# SCH_-_Compute_Flash.net
KiCad netlist of a schematic drawn in Altium Designer
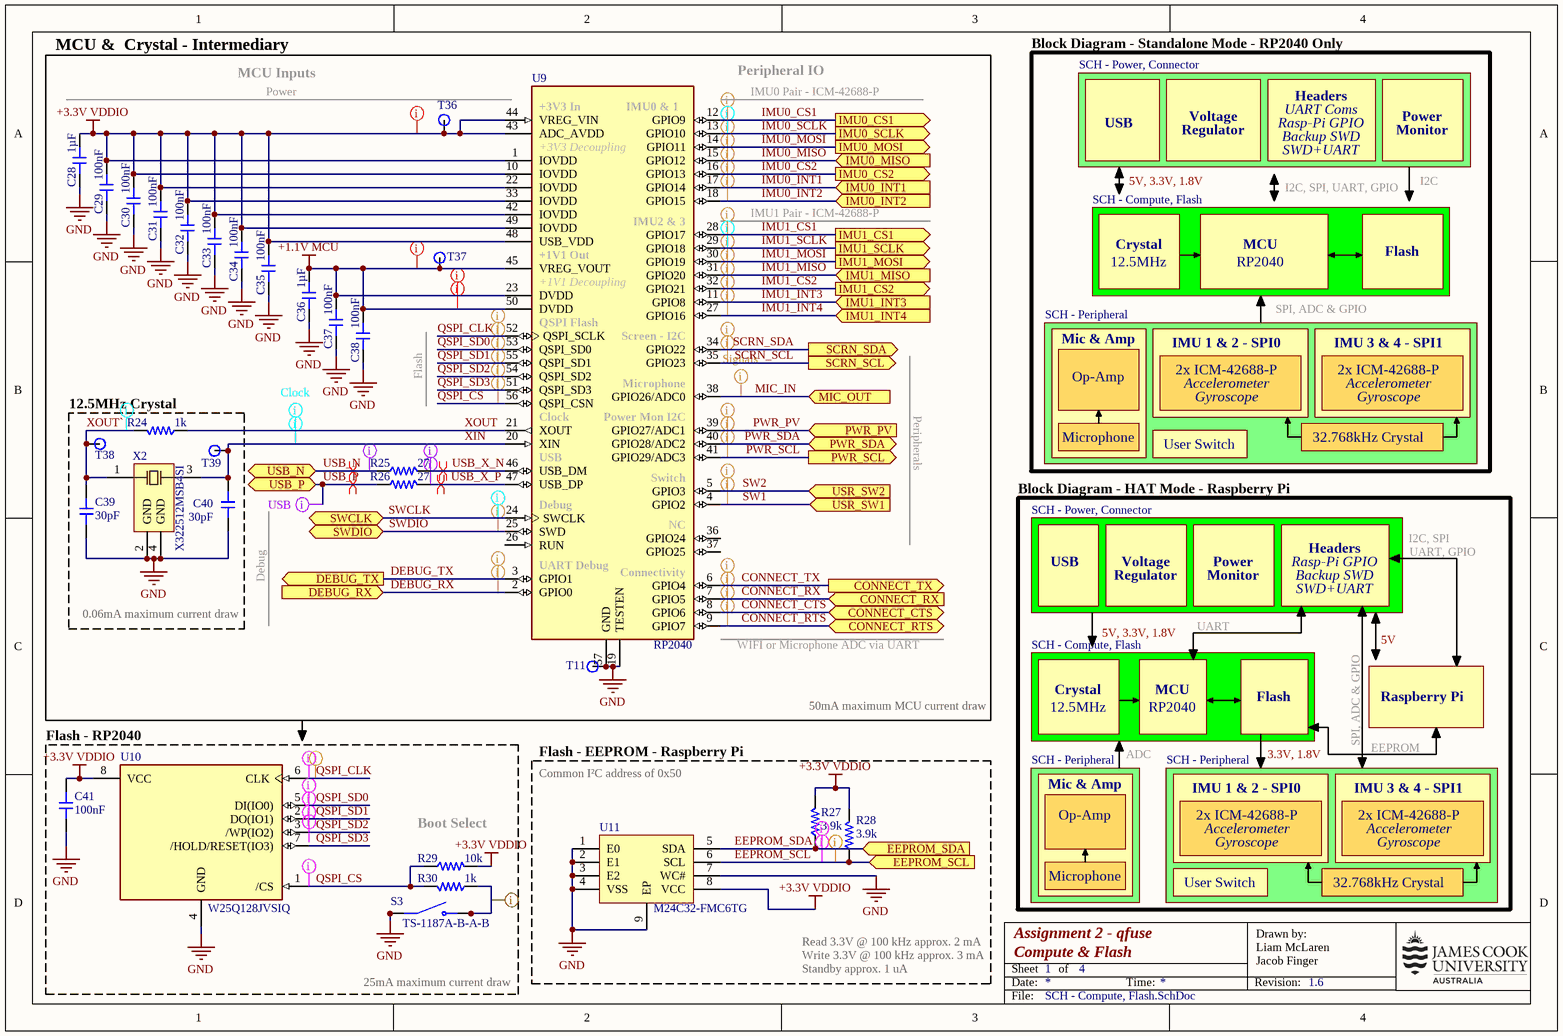
[diagram p0: SCH - Compute, Flash.SchDoc]

(export (version "E")
  (design (tool "Eeschema 10.0.6"))
  (components
    (comp (ref "C28")
      (value "1µF")
      (footprint "CAP-0402")
      (description "Capacitor, Ceramic (MLCC), 1uF, ±10%, 25V, X5R, ±10%, SMD 0402")
      (fields
        (field (name "JLCPCB BASIC PART") "Yes")
        (field (name "MANUFACTURER") "Samsung Electro-Mechanics")
      )
      (libsource (lib "Finmac Systems") (part "GRM21BR61H106KE43L"))
    )
    (comp (ref "C29")
      (value "100nF")
      (footprint "CAP-0402")
      (description "Capacitor, Ceramic (MLCC), 100nF, ±10%, 50V, X7R, ±10%, SMD 0402")
      (fields
        (field (name "MANUFACTURER PART NUMBER") "CL05B104KB54PNC")
        (field (name "MANUFACTURER") "Samsung Electro-Mechanics")
      )
      (libsource (lib "Finmac Systems") (part "GRM21BR61H106KE43L"))
    )
    (comp (ref "C30")
      (value "100nF")
      (footprint "CAP-0402")
      (description "Capacitor, Ceramic (MLCC), 100nF, ±10%, 50V, X7R, ±10%, SMD 0402")
      (fields
        (field (name "MANUFACTURER PART NUMBER") "CL05B104KB54PNC")
        (field (name "MANUFACTURER") "Samsung Electro-Mechanics")
      )
      (libsource (lib "Finmac Systems") (part "GRM21BR61H106KE43L"))
    )
    (comp (ref "C31")
      (value "100nF")
      (footprint "CAP-0402")
      (description "Capacitor, Ceramic (MLCC), 100nF, ±10%, 50V, X7R, ±10%, SMD 0402")
      (fields
        (field (name "MANUFACTURER PART NUMBER") "CL05B104KB54PNC")
        (field (name "MANUFACTURER") "Samsung Electro-Mechanics")
      )
      (libsource (lib "Finmac Systems") (part "GRM21BR61H106KE43L"))
    )
    (comp (ref "C32")
      (value "100nF")
      (footprint "CAP-0402")
      (description "Capacitor, Ceramic (MLCC), 100nF, ±10%, 50V, X7R, ±10%, SMD 0402")
      (fields
        (field (name "MANUFACTURER PART NUMBER") "CL05B104KB54PNC")
        (field (name "MANUFACTURER") "Samsung Electro-Mechanics")
      )
      (libsource (lib "Finmac Systems") (part "GRM21BR61H106KE43L"))
    )
    (comp (ref "C33")
      (value "100nF")
      (footprint "CAP-0402")
      (description "Capacitor, Ceramic (MLCC), 100nF, ±10%, 50V, X7R, ±10%, SMD 0402")
      (fields
        (field (name "MANUFACTURER PART NUMBER") "CL05B104KB54PNC")
        (field (name "MANUFACTURER") "Samsung Electro-Mechanics")
      )
      (libsource (lib "Finmac Systems") (part "GRM21BR61H106KE43L"))
    )
    (comp (ref "C34")
      (value "100nF")
      (footprint "CAP-0402")
      (description "Capacitor, Ceramic (MLCC), 100nF, ±10%, 50V, X7R, ±10%, SMD 0402")
      (fields
        (field (name "MANUFACTURER PART NUMBER") "CL05B104KB54PNC")
        (field (name "MANUFACTURER") "Samsung Electro-Mechanics")
      )
      (libsource (lib "Finmac Systems") (part "GRM21BR61H106KE43L"))
    )
    (comp (ref "C35")
      (value "100nF")
      (footprint "CAP-0402")
      (description "Capacitor, Ceramic (MLCC), 100nF, ±10%, 50V, X7R, ±10%, SMD 0402")
      (fields
        (field (name "MANUFACTURER PART NUMBER") "CL05B104KB54PNC")
        (field (name "MANUFACTURER") "Samsung Electro-Mechanics")
      )
      (libsource (lib "Finmac Systems") (part "GRM21BR61H106KE43L"))
    )
    (comp (ref "C36")
      (value "1µF")
      (footprint "CAP-0402")
      (description "Capacitor, Ceramic (MLCC), 1uF, ±10%, 25V, X5R, ±10%, SMD 0402")
      (fields
        (field (name "JLCPCB BASIC PART") "Yes")
        (field (name "MANUFACTURER") "Samsung Electro-Mechanics")
      )
      (libsource (lib "Finmac Systems") (part "GRM21BR61H106KE43L"))
    )
    (comp (ref "C37")
      (value "100nF")
      (footprint "CAP-0402")
      (description "Capacitor, Ceramic (MLCC), 100nF, ±10%, 50V, X7R, ±10%, SMD 0402")
      (fields
        (field (name "MANUFACTURER PART NUMBER") "CL05B104KB54PNC")
        (field (name "MANUFACTURER") "Samsung Electro-Mechanics")
      )
      (libsource (lib "Finmac Systems") (part "GRM21BR61H106KE43L"))
    )
    (comp (ref "C38")
      (value "100nF")
      (footprint "CAP-0402")
      (description "Capacitor, Ceramic (MLCC), 100nF, ±10%, 50V, X7R, ±10%, SMD 0402")
      (fields
        (field (name "MANUFACTURER PART NUMBER") "CL05B104KB54PNC")
        (field (name "MANUFACTURER") "Samsung Electro-Mechanics")
      )
      (libsource (lib "Finmac Systems") (part "GRM21BR61H106KE43L"))
    )
    (comp (ref "C39")
      (value "30pF")
      (footprint "CAP-0603")
      (description "Capacitor, Ceramic (MLCC), 30pF, ±5%, 50V, C0G, ±5%, SMD 0603")
      (fields (field (name "JLCPCB PART NUMBER") "C1658") (field (name "TOLERANCE") "5%"))
      (libsource (lib "Finmac Systems") (part "GRM21BR61H106KE43L"))
    )
    (comp (ref "C40")
      (value "30pF")
      (footprint "CAP-0603")
      (description "Capacitor, Ceramic (MLCC), 30pF, ±5%, 50V, C0G, ±5%, SMD 0603")
      (fields (field (name "JLCPCB PART NUMBER") "C1658") (field (name "TOLERANCE") "5%"))
      (libsource (lib "Finmac Systems") (part "GRM21BR61H106KE43L"))
    )
    (comp (ref "C41")
      (value "100nF")
      (footprint "CAP-0402")
      (description "Capacitor, Ceramic (MLCC), 100nF, ±10%, 50V, X7R, ±10%, SMD 0402")
      (fields
        (field (name "MANUFACTURER PART NUMBER") "CL05B104KB54PNC")
        (field (name "MANUFACTURER") "Samsung Electro-Mechanics")
      )
      (libsource (lib "Finmac Systems") (part "GRM21BR61H106KE43L"))
    )
    (comp (ref "R24")
      (value "1k")
      (footprint "RES-0402")
      (description "Resistor, 1kΩ, ±1%, 62.5mW, 50V, ±100ppm/℃, -55℃~+155℃, SMD 0402")
      (fields (field (name "JLCPCB PART NUMBER") "C11702") (field (name "JLCPCB BASIC PART") "Yes"))
      (libsource (lib "Finmac Systems") (part "1206W4F7500T5E"))
    )
    (comp (ref "R25")
      (value "27")
      (footprint "RES-0603")
      (description "Resistor, 27Ω, ±1%, 100mW, 75V, ±200ppm/℃, -55℃~+155℃, SMD 0603")
      (fields (field (name "MANUFACTURER") "Uniroyal") (field (name "JLCPCB PART NUMBER") "C25190"))
      (libsource (lib "Finmac Systems") (part "1206W4F7500T5E"))
    )
    (comp (ref "R26")
      (value "27")
      (footprint "RES-0603")
      (description "Resistor, 27Ω, ±1%, 100mW, 75V, ±200ppm/℃, -55℃~+155℃, SMD 0603")
      (fields (field (name "MANUFACTURER") "Uniroyal") (field (name "JLCPCB PART NUMBER") "C25190"))
      (libsource (lib "Finmac Systems") (part "1206W4F7500T5E"))
    )
    (comp (ref "R27")
      (value "3.9k")
      (footprint "RES-0402")
      (description "Resistor, 3.9kΩ, ±1%, 62.5mW, 50V, ±100ppm/℃, -55℃~+155℃, SMD 0402")
      (fields (field (name "MANUFACTURER PART NUMBER") "0402WGF3901TCE") (field (name "TOLERANCE") "1%"))
      (libsource (lib "Finmac Systems") (part "1206W4F7500T5E"))
    )
    (comp (ref "R28")
      (value "3.9k")
      (footprint "RES-0402")
      (description "Resistor, 3.9kΩ, ±1%, 62.5mW, 50V, ±100ppm/℃, -55℃~+155℃, SMD 0402")
      (fields (field (name "MANUFACTURER PART NUMBER") "0402WGF3901TCE") (field (name "TOLERANCE") "1%"))
      (libsource (lib "Finmac Systems") (part "1206W4F7500T5E"))
    )
    (comp (ref "R29")
      (value "10k")
      (footprint "RES-0402")
      (description "Resistor, 10kΩ, ±1%, 62.5mW, 50V, ±100ppm/℃, -55℃~+155℃, SMD 0402")
      (fields (field (name "JLCPCB BASIC PART") "Yes") (field (name "MANUFACTURER") "Uniroyal"))
      (libsource (lib "Finmac Systems") (part "1206W4F7500T5E"))
    )
    (comp (ref "R30")
      (value "1k")
      (footprint "RES-0402")
      (description "Resistor, 1kΩ, ±1%, 62.5mW, 50V, ±100ppm/℃, -55℃~+155℃, SMD 0402")
      (fields (field (name "JLCPCB PART NUMBER") "C11702") (field (name "JLCPCB BASIC PART") "Yes"))
      (libsource (lib "Finmac Systems") (part "1206W4F7500T5E"))
    )
    (comp (ref "S3")
      (value "TS-1187A-B-A-B")
      (footprint "SW_TS-1187A-B-A-B")
      (description "SPST 50mA @ 12VDC Top Actuated Round Button 160gf SMD Tactile Switches RoHS")
      (fields (field (name "JLCPCB PART NUMBER") "C318884"))
      (libsource (lib "qfuse_sch_lib") (part "CMP-051-000000-5"))
    )
    (comp (ref "T11")
      (value "TP")
      (footprint "TestPoint")
      (libsource (lib "DatumPenLibrary") (part "TestPoint"))
    )
    (comp (ref "T36")
      (value "TP")
      (footprint "TestPoint")
      (libsource (lib "DatumPenLibrary") (part "TestPoint"))
    )
    (comp (ref "T37")
      (value "TP")
      (footprint "TestPoint")
      (libsource (lib "DatumPenLibrary") (part "TestPoint"))
    )
    (comp (ref "T38")
      (value "TP")
      (footprint "TestPoint")
      (libsource (lib "DatumPenLibrary") (part "TestPoint"))
    )
    (comp (ref "T39")
      (value "TP")
      (footprint "TestPoint")
      (libsource (lib "DatumPenLibrary") (part "TestPoint"))
    )
    (comp (ref "U9")
      (value "RP2040")
      (footprint "QFN40P700X700X90-57N")
      (description "ARM Cortex-M0+ MCU 32-Bit Microcontroller for Raspberry Pi Pico")
      (fields (field (name "JLCPCB PART NUMBER") "C2040"))
      (libsource (lib "qfuse_sch_lib") (part "CMP-043-000000-5"))
    )
    (comp (ref "U10")
      (value "W25Q128JVSIQ")
      (footprint "SOIC127P790X216-8N")
      (description "FLASH - NOR Memory IC 128Mb (16M x 8) SPI - Quad I/O, QPI, DTR 133 MHz 8-SOIC")
      (fields (field (name "MF") "Winbond Electronics") (field (name "JLCPCB PART NUMBER") "C97521"))
      (libsource (lib "qfuse_sch_lib") (part "CMP-031-00006-4"))
    )
    (comp (ref "U11")
      (value "M24C32-FMC6TG")
      (footprint "M24C32-FMC6TG")
      (description "STMicroelectronics M24C32-FMC6TG - UFDFPN-8(2x3) - 32Kbit I2C UFDFPN-8(2x3) EEPROM ROHS")
      (fields (field (name "JLCPCB PART NUMBER") "C2060985"))
      (libsource (lib "qfuse_sch_lib") (part "M24C32-FMC6TG"))
    )
    (comp (ref "X2")
      (value "X322512MSB4SI")
      (footprint "X322512MSB4SI-Footprint-1")
      (description "12MHz SMD Crystal Resonator 20pF ±10ppm ±30ppm -40℃~+85℃ SMD3225-4P  Crystals ROHS Yangxing Tech")
      (fields (field (name "JLCPCB PART NUMBER") "C9002"))
      (libsource (lib "qfuse_sch_lib") (part "CMP-00002-4"))
    )
  )
  (nets
    (net (code "1") (name "+1.1V MCU") (class "Default")
      (node (ref "C36") (pin "1") (pinfunction "1_1") (pintype "passive"))
      (node (ref "C37") (pin "2") (pinfunction "2_2") (pintype "passive"))
      (node (ref "C38") (pin "2") (pinfunction "2_2") (pintype "passive"))
      (node (ref "T37") (pin "1") (pinfunction "TP_1") (pintype "passive"))
      (node (ref "U9") (pin "23") (pinfunction "DVDD_23") (pintype "power_in"))
      (node (ref "U9") (pin "45") (pinfunction "VREG_VOUT_45") (pintype "power_in"))
      (node (ref "U9") (pin "50") (pinfunction "DVDD_50") (pintype "power_in"))
    )
    (net (code "2") (name "+3.3V VDDIO") (class "Default")
      (node (ref "C28") (pin "2") (pinfunction "2_2") (pintype "passive"))
      (node (ref "C29") (pin "2") (pinfunction "2_2") (pintype "passive"))
      (node (ref "C30") (pin "2") (pinfunction "2_2") (pintype "passive"))
      (node (ref "C31") (pin "2") (pinfunction "2_2") (pintype "passive"))
      (node (ref "C32") (pin "2") (pinfunction "2_2") (pintype "passive"))
      (node (ref "C33") (pin "2") (pinfunction "2_2") (pintype "passive"))
      (node (ref "C34") (pin "2") (pinfunction "2_2") (pintype "passive"))
      (node (ref "C35") (pin "2") (pinfunction "2_2") (pintype "passive"))
      (node (ref "C41") (pin "2") (pinfunction "2_2") (pintype "passive"))
      (node (ref "R27") (pin "2") (pinfunction "2_2") (pintype "passive"))
      (node (ref "R28") (pin "2") (pinfunction "2_2") (pintype "passive"))
      (node (ref "R29") (pin "2") (pinfunction "2_2") (pintype "passive"))
      (node (ref "T36") (pin "1") (pinfunction "TP_1") (pintype "passive"))
      (node (ref "U10") (pin "8") (pinfunction "VCC_8") (pintype "power_in"))
      (node (ref "U11") (pin "8") (pinfunction "VCC_8") (pintype "passive"))
      (node (ref "U9") (pin "1") (pinfunction "IOVDD_1") (pintype "power_in"))
      (node (ref "U9") (pin "10") (pinfunction "IOVDD_10") (pintype "power_in"))
      (node (ref "U9") (pin "22") (pinfunction "IOVDD_22") (pintype "power_in"))
      (node (ref "U9") (pin "33") (pinfunction "IOVDD_33") (pintype "power_in"))
      (node (ref "U9") (pin "42") (pinfunction "IOVDD_42") (pintype "power_in"))
      (node (ref "U9") (pin "43") (pinfunction "ADC_AVDD_43") (pintype "power_in"))
      (node (ref "U9") (pin "44") (pinfunction "VREG_VIN_44") (pintype "input"))
      (node (ref "U9") (pin "48") (pinfunction "USB_VDD_48") (pintype "power_in"))
      (node (ref "U9") (pin "49") (pinfunction "IOVDD_49") (pintype "power_in"))
    )
    (net (code "3") (name "/CONNECT_CTS") (class "Default")
      (node (ref "U9") (pin "8") (pinfunction "GPIO6_8") (pintype "bidirectional"))
    )
    (net (code "4") (name "/CONNECT_RTS") (class "Default")
      (node (ref "U9") (pin "9") (pinfunction "GPIO7_9") (pintype "bidirectional"))
    )
    (net (code "5") (name "/CONNECT_RX") (class "Default")
      (node (ref "U9") (pin "7") (pinfunction "GPIO5_7") (pintype "bidirectional"))
    )
    (net (code "6") (name "/CONNECT_TX") (class "Default")
      (node (ref "U9") (pin "6") (pinfunction "GPIO4_6") (pintype "bidirectional"))
    )
    (net (code "7") (name "/DEBUG_RX") (class "Default")
      (node (ref "U9") (pin "2") (pinfunction "GPIO0_2") (pintype "bidirectional"))
    )
    (net (code "8") (name "/DEBUG_TX") (class "Default")
      (node (ref "U9") (pin "3") (pinfunction "GPIO1_3") (pintype "bidirectional"))
    )
    (net (code "9") (name "/EEPROM_SCL") (class "Default")
      (node (ref "R28") (pin "1") (pinfunction "1_1") (pintype "passive"))
      (node (ref "U11") (pin "6") (pinfunction "SCL_6") (pintype "passive"))
    )
    (net (code "10") (name "/EEPROM_SDA") (class "Default")
      (node (ref "R27") (pin "1") (pinfunction "1_1") (pintype "passive"))
      (node (ref "U11") (pin "5") (pinfunction "SDA_5") (pintype "passive"))
    )
    (net (code "11") (name "/IMU0_CS1") (class "Default")
      (node (ref "U9") (pin "12") (pinfunction "GPIO9_12") (pintype "bidirectional"))
    )
    (net (code "12") (name "/IMU0_CS2") (class "Default")
      (node (ref "U9") (pin "16") (pinfunction "GPIO13_16") (pintype "bidirectional"))
    )
    (net (code "13") (name "/IMU0_INT1") (class "Default")
      (node (ref "U9") (pin "17") (pinfunction "GPIO14_17") (pintype "bidirectional"))
    )
    (net (code "14") (name "/IMU0_INT2") (class "Default")
      (node (ref "U9") (pin "18") (pinfunction "GPIO15_18") (pintype "bidirectional"))
    )
    (net (code "15") (name "/IMU0_MISO") (class "Default")
      (node (ref "U9") (pin "15") (pinfunction "GPIO12_15") (pintype "bidirectional"))
    )
    (net (code "16") (name "/IMU0_MOSI") (class "Default")
      (node (ref "U9") (pin "14") (pinfunction "GPIO11_14") (pintype "bidirectional"))
    )
    (net (code "17") (name "/IMU0_SCLK") (class "Default")
      (node (ref "U9") (pin "13") (pinfunction "GPIO10_13") (pintype "bidirectional"))
    )
    (net (code "18") (name "/IMU1_CS1") (class "Default")
      (node (ref "U9") (pin "28") (pinfunction "GPIO17_28") (pintype "bidirectional"))
    )
    (net (code "19") (name "/IMU1_CS2") (class "Default")
      (node (ref "U9") (pin "32") (pinfunction "GPIO21_32") (pintype "bidirectional"))
    )
    (net (code "20") (name "/IMU1_INT3") (class "Default")
      (node (ref "U9") (pin "11") (pinfunction "GPIO8_11") (pintype "bidirectional"))
    )
    (net (code "21") (name "/IMU1_INT4") (class "Default")
      (node (ref "U9") (pin "27") (pinfunction "GPIO16_27") (pintype "bidirectional"))
    )
    (net (code "22") (name "/IMU1_MISO") (class "Default")
      (node (ref "U9") (pin "31") (pinfunction "GPIO20_31") (pintype "bidirectional"))
    )
    (net (code "23") (name "/IMU1_MOSI") (class "Default")
      (node (ref "U9") (pin "30") (pinfunction "GPIO19_30") (pintype "bidirectional"))
    )
    (net (code "24") (name "/IMU1_SCLK") (class "Default")
      (node (ref "U9") (pin "29") (pinfunction "GPIO18_29") (pintype "bidirectional"))
    )
    (net (code "25") (name "/MIC_IN") (class "Default")
      (node (ref "U9") (pin "38") (pinfunction "GPIO26/ADC0_38") (pintype "bidirectional"))
    )
    (net (code "26") (name "/PWR_PV") (class "Default")
      (node (ref "U9") (pin "39") (pinfunction "GPIO27/ADC1_39") (pintype "bidirectional"))
    )
    (net (code "27") (name "/PWR_SCL") (class "Default")
      (node (ref "U9") (pin "41") (pinfunction "GPIO29/ADC3_41") (pintype "bidirectional"))
    )
    (net (code "28") (name "/PWR_SDA") (class "Default")
      (node (ref "U9") (pin "40") (pinfunction "GPIO28/ADC2_40") (pintype "bidirectional"))
    )
    (net (code "29") (name "/QSPI_CLK") (class "Default")
      (node (ref "U10") (pin "6") (pinfunction "CLK_6") (pintype "input"))
      (node (ref "U9") (pin "52") (pinfunction "QSPI_SCLK_52") (pintype "bidirectional"))
    )
    (net (code "30") (name "/QSPI_CS") (class "Default")
      (node (ref "R29") (pin "1") (pinfunction "1_1") (pintype "passive"))
      (node (ref "R30") (pin "2") (pinfunction "2_2") (pintype "passive"))
      (node (ref "U10") (pin "1") (pinfunction "/CS_1") (pintype "input"))
      (node (ref "U9") (pin "56") (pinfunction "QSPI_CSN_56") (pintype "bidirectional"))
    )
    (net (code "31") (name "/QSPI_SD0") (class "Default")
      (node (ref "U10") (pin "5") (pinfunction "DI(IO0)_5") (pintype "bidirectional"))
      (node (ref "U9") (pin "53") (pinfunction "QSPI_SD0_53") (pintype "bidirectional"))
    )
    (net (code "32") (name "/QSPI_SD1") (class "Default")
      (node (ref "U10") (pin "2") (pinfunction "DO(IO1)_2") (pintype "bidirectional"))
      (node (ref "U9") (pin "55") (pinfunction "QSPI_SD1_55") (pintype "bidirectional"))
    )
    (net (code "33") (name "/QSPI_SD2") (class "Default")
      (node (ref "U10") (pin "3") (pinfunction "/WP(IO2)_3") (pintype "bidirectional"))
      (node (ref "U9") (pin "54") (pinfunction "QSPI_SD2_54") (pintype "bidirectional"))
    )
    (net (code "34") (name "/QSPI_SD3") (class "Default")
      (node (ref "U10") (pin "7") (pinfunction "/HOLD/RESET(IO3)_7") (pintype "bidirectional"))
      (node (ref "U9") (pin "51") (pinfunction "QSPI_SD3_51") (pintype "bidirectional"))
    )
    (net (code "35") (name "/SCRN_SCL") (class "Default")
      (node (ref "U9") (pin "35") (pinfunction "GPIO23_35") (pintype "bidirectional"))
    )
    (net (code "36") (name "/SCRN_SDA") (class "Default")
      (node (ref "U9") (pin "34") (pinfunction "GPIO22_34") (pintype "bidirectional"))
    )
    (net (code "37") (name "/SW1") (class "Default")
      (node (ref "U9") (pin "4") (pinfunction "GPIO2_4") (pintype "bidirectional"))
    )
    (net (code "38") (name "/SW2") (class "Default")
      (node (ref "U9") (pin "5") (pinfunction "GPIO3_5") (pintype "bidirectional"))
    )
    (net (code "39") (name "/SWCLK") (class "Default")
      (node (ref "U9") (pin "24") (pinfunction "SWCLK_24") (pintype "input"))
    )
    (net (code "40") (name "/SWDIO") (class "Default")
      (node (ref "U9") (pin "25") (pinfunction "SWD_25") (pintype "bidirectional"))
    )
    (net (code "41") (name "/USB_N") (class "Default")
      (node (ref "R25") (pin "1") (pinfunction "1_1") (pintype "passive"))
    )
    (net (code "42") (name "/USB_P") (class "Default")
      (node (ref "R26") (pin "1") (pinfunction "1_1") (pintype "passive"))
    )
    (net (code "43") (name "/USB_X_N") (class "Default")
      (node (ref "R25") (pin "2") (pinfunction "2_2") (pintype "passive"))
      (node (ref "U9") (pin "46") (pinfunction "USB_DM_46") (pintype "bidirectional"))
    )
    (net (code "44") (name "/USB_X_P") (class "Default")
      (node (ref "R26") (pin "2") (pinfunction "2_2") (pintype "passive"))
      (node (ref "U9") (pin "47") (pinfunction "USB_DP_47") (pintype "bidirectional"))
    )
    (net (code "45") (name "/XIN") (class "Default")
      (node (ref "C40") (pin "2") (pinfunction "2_2") (pintype "passive"))
      (node (ref "T39") (pin "1") (pinfunction "TP_1") (pintype "passive"))
      (node (ref "U9") (pin "20") (pinfunction "XIN_20") (pintype "input"))
      (node (ref "X2") (pin "3") (pinfunction "OSC2_3") (pintype "passive"))
    )
    (net (code "46") (name "/XOUT") (class "Default")
      (node (ref "R24") (pin "1") (pinfunction "1_1") (pintype "passive"))
      (node (ref "U9") (pin "21") (pinfunction "XOUT_21") (pintype "output"))
    )
    (net (code "47") (name "/XOUT`") (class "Default")
      (node (ref "C39") (pin "2") (pinfunction "2_2") (pintype "passive"))
      (node (ref "R24") (pin "2") (pinfunction "2_2") (pintype "passive"))
      (node (ref "T38") (pin "1") (pinfunction "TP_1") (pintype "passive"))
      (node (ref "X2") (pin "1") (pinfunction "OSC1_1") (pintype "passive"))
    )
    (net (code "48") (name "GND") (class "Default")
      (node (ref "C28") (pin "1") (pinfunction "1_1") (pintype "passive"))
      (node (ref "C29") (pin "1") (pinfunction "1_1") (pintype "passive"))
      (node (ref "C30") (pin "1") (pinfunction "1_1") (pintype "passive"))
      (node (ref "C31") (pin "1") (pinfunction "1_1") (pintype "passive"))
      (node (ref "C32") (pin "1") (pinfunction "1_1") (pintype "passive"))
      (node (ref "C33") (pin "1") (pinfunction "1_1") (pintype "passive"))
      (node (ref "C34") (pin "1") (pinfunction "1_1") (pintype "passive"))
      (node (ref "C35") (pin "1") (pinfunction "1_1") (pintype "passive"))
      (node (ref "C36") (pin "2") (pinfunction "2_2") (pintype "passive"))
      (node (ref "C37") (pin "1") (pinfunction "1_1") (pintype "passive"))
      (node (ref "C38") (pin "1") (pinfunction "1_1") (pintype "passive"))
      (node (ref "C39") (pin "1") (pinfunction "1_1") (pintype "passive"))
      (node (ref "C40") (pin "1") (pinfunction "1_1") (pintype "passive"))
      (node (ref "C41") (pin "1") (pinfunction "1_1") (pintype "passive"))
      (node (ref "S3") (pin "A") (pinfunction "COM_A") (pintype "passive"))
      (node (ref "S3") (pin "B") (pinfunction "COM_B") (pintype "passive"))
      (node (ref "T11") (pin "1") (pinfunction "TP_1") (pintype "passive"))
      (node (ref "U10") (pin "4") (pinfunction "GND_4") (pintype "power_in"))
      (node (ref "U11") (pin "1") (pinfunction "E0_1") (pintype "passive"))
      (node (ref "U11") (pin "2") (pinfunction "E1_2") (pintype "passive"))
      (node (ref "U11") (pin "3") (pinfunction "E2_3") (pintype "passive"))
      (node (ref "U11") (pin "4") (pinfunction "VSS_4") (pintype "passive"))
      (node (ref "U11") (pin "7") (pinfunction "WC#_7") (pintype "passive"))
      (node (ref "U11") (pin "9") (pinfunction "EP_9") (pintype "passive"))
      (node (ref "U9") (pin "19") (pinfunction "TESTEN_19") (pintype "passive"))
      (node (ref "U9") (pin "57") (pinfunction "GND_57") (pintype "power_in"))
      (node (ref "X2") (pin "2") (pinfunction "GND_2") (pintype "passive"))
      (node (ref "X2") (pin "4") (pinfunction "GND_4") (pintype "passive"))
    )
    (net (code "49") (name "Net-(R30-Pad1)") (class "Default")
      (node (ref "R30") (pin "1") (pinfunction "1_1") (pintype "passive"))
      (node (ref "S3") (pin "C") (pinfunction "NO_C") (pintype "passive"))
      (node (ref "S3") (pin "D") (pinfunction "NO_D") (pintype "passive"))
    )
    (net (code "50") (name "unconnected-(U9-GPIO24-Pad36)") (class "Default")
      (node (ref "U9") (pin "36") (pinfunction "GPIO24_36") (pintype "bidirectional"))
    )
    (net (code "51") (name "unconnected-(U9-GPIO25-Pad37)") (class "Default")
      (node (ref "U9") (pin "37") (pinfunction "GPIO25_37") (pintype "bidirectional"))
    )
    (net (code "52") (name "unconnected-(U9-RUN-Pad26)") (class "Default")
      (node (ref "U9") (pin "26") (pinfunction "RUN_26") (pintype "input"))
    )
  )
)
